# DigiPCJoy.net
KiCad netlist of a schematic drawn in EAGLE
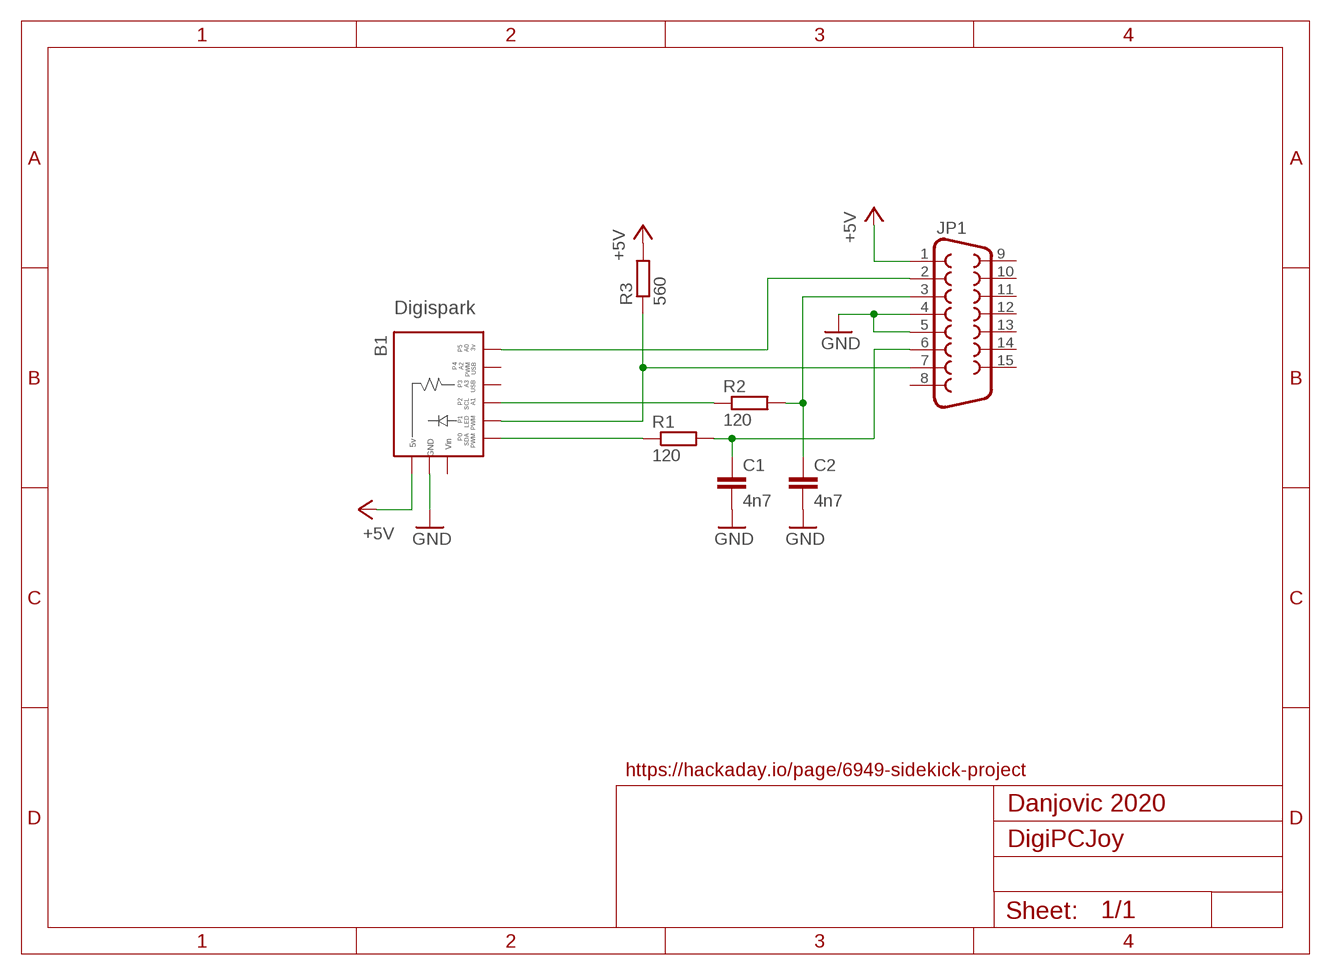
[diagram p0: schematic, sheet 1]

(export (version "E")
  (design (tool "Eeschema 10.0.6"))
  (components
    (comp (ref "B1")
      (value "Digispark")
      (footprint "eagle-import:DIGISPARK_SOCKET")
      (libsource (lib "eagle-import") (part "DIGISPARK-SOCKET"))
    )
    (comp (ref "C1")
      (value "4n7")
      (footprint "eagle-import:C050-024X044")
      (libsource (lib "eagle-import") (part "C-EU050-024X044"))
    )
    (comp (ref "C2")
      (value "4n7")
      (footprint "eagle-import:C050-024X044")
      (libsource (lib "eagle-import") (part "C-EU050-024X044"))
    )
    (comp (ref "JP1")
      (value "F15H")
      (footprint "eagle-import:F15H")
      (libsource (lib "eagle-import") (part "F15H"))
    )
    (comp (ref "R1")
      (value "120")
      (footprint "eagle-import:0204_7")
      (libsource (lib "eagle-import") (part "R-EU_0204/7"))
    )
    (comp (ref "R2")
      (value "120")
      (footprint "eagle-import:0204_7")
      (libsource (lib "eagle-import") (part "R-EU_0204/7"))
    )
    (comp (ref "R3")
      (value "560")
      (footprint "eagle-import:0204_7")
      (libsource (lib "eagle-import") (part "R-EU_0204/7"))
    )
  )
  (nets
    (net (code "1") (name "+5V") (class "Default")
      (node (ref "B1") (pin "5V") (pinfunction "5V_5V") (pintype "power_in"))
      (node (ref "JP1") (pin "1") (pinfunction "1_1") (pintype "passive"))
      (node (ref "R3") (pin "2") (pinfunction "2_2") (pintype "passive"))
    )
    (net (code "2") (name "/VIN") (class "Default")
      (node (ref "B1") (pin "VIN") (pinfunction "VIN_VIN") (pintype "power_in"))
    )
    (net (code "3") (name "GND") (class "Default")
      (node (ref "B1") (pin "GND") (pinfunction "GND_GND") (pintype "power_in"))
      (node (ref "C1") (pin "2") (pinfunction "2_2") (pintype "passive"))
      (node (ref "C2") (pin "2") (pinfunction "2_2") (pintype "passive"))
      (node (ref "JP1") (pin "4") (pinfunction "4_4") (pintype "passive"))
      (node (ref "JP1") (pin "5") (pinfunction "5_5") (pintype "passive"))
    )
    (net (code "4") (name "Net-(B1-PadP0)") (class "Default")
      (node (ref "B1") (pin "P0") (pinfunction "P0_P0") (pintype "bidirectional"))
      (node (ref "R1") (pin "1") (pinfunction "1_1") (pintype "passive"))
    )
    (net (code "5") (name "Net-(B1-PadP1)") (class "Default")
      (node (ref "B1") (pin "P1") (pinfunction "P1_P1") (pintype "bidirectional"))
      (node (ref "JP1") (pin "7") (pinfunction "7_7") (pintype "passive"))
      (node (ref "R3") (pin "1") (pinfunction "1_1") (pintype "passive"))
    )
    (net (code "6") (name "Net-(B1-PadP2)") (class "Default")
      (node (ref "B1") (pin "P2") (pinfunction "P2_P2") (pintype "bidirectional"))
      (node (ref "R2") (pin "1") (pinfunction "1_1") (pintype "passive"))
    )
    (net (code "7") (name "Net-(B1-PadP5)") (class "Default")
      (node (ref "B1") (pin "P5") (pinfunction "P5_P5") (pintype "bidirectional"))
      (node (ref "JP1") (pin "2") (pinfunction "2_2") (pintype "passive"))
    )
    (net (code "8") (name "Net-(C1-Pad1)") (class "Default")
      (node (ref "C1") (pin "1") (pinfunction "1_1") (pintype "passive"))
      (node (ref "JP1") (pin "6") (pinfunction "6_6") (pintype "passive"))
      (node (ref "R1") (pin "2") (pinfunction "2_2") (pintype "passive"))
    )
    (net (code "9") (name "Net-(C2-Pad1)") (class "Default")
      (node (ref "C2") (pin "1") (pinfunction "1_1") (pintype "passive"))
      (node (ref "JP1") (pin "3") (pinfunction "3_3") (pintype "passive"))
      (node (ref "R2") (pin "2") (pinfunction "2_2") (pintype "passive"))
    )
    (net (code "10") (name "unconnected-(B1-PadP3)") (class "Default")
      (node (ref "B1") (pin "P3") (pinfunction "P3_P3") (pintype "bidirectional"))
    )
    (net (code "11") (name "unconnected-(B1-PadP4)") (class "Default")
      (node (ref "B1") (pin "P4") (pinfunction "P4_P4") (pintype "bidirectional"))
    )
    (net (code "12") (name "unconnected-(JP1-Pad8)") (class "Default")
      (node (ref "JP1") (pin "8") (pinfunction "8_8") (pintype "passive"))
    )
    (net (code "13") (name "unconnected-(JP1-Pad9)") (class "Default")
      (node (ref "JP1") (pin "9") (pinfunction "9_9") (pintype "passive"))
    )
    (net (code "14") (name "unconnected-(JP1-Pad10)") (class "Default")
      (node (ref "JP1") (pin "10") (pinfunction "10_10") (pintype "passive"))
    )
    (net (code "15") (name "unconnected-(JP1-Pad11)") (class "Default")
      (node (ref "JP1") (pin "11") (pinfunction "11_11") (pintype "passive"))
    )
    (net (code "16") (name "unconnected-(JP1-Pad12)") (class "Default")
      (node (ref "JP1") (pin "12") (pinfunction "12_12") (pintype "passive"))
    )
    (net (code "17") (name "unconnected-(JP1-Pad13)") (class "Default")
      (node (ref "JP1") (pin "13") (pinfunction "13_13") (pintype "passive"))
    )
    (net (code "18") (name "unconnected-(JP1-Pad14)") (class "Default")
      (node (ref "JP1") (pin "14") (pinfunction "14_14") (pintype "passive"))
    )
    (net (code "19") (name "unconnected-(JP1-Pad15)") (class "Default")
      (node (ref "JP1") (pin "15") (pinfunction "15_15") (pintype "passive"))
    )
  )
)
